# Connection.net
KiCad netlist of a schematic drawn in Altium Designer
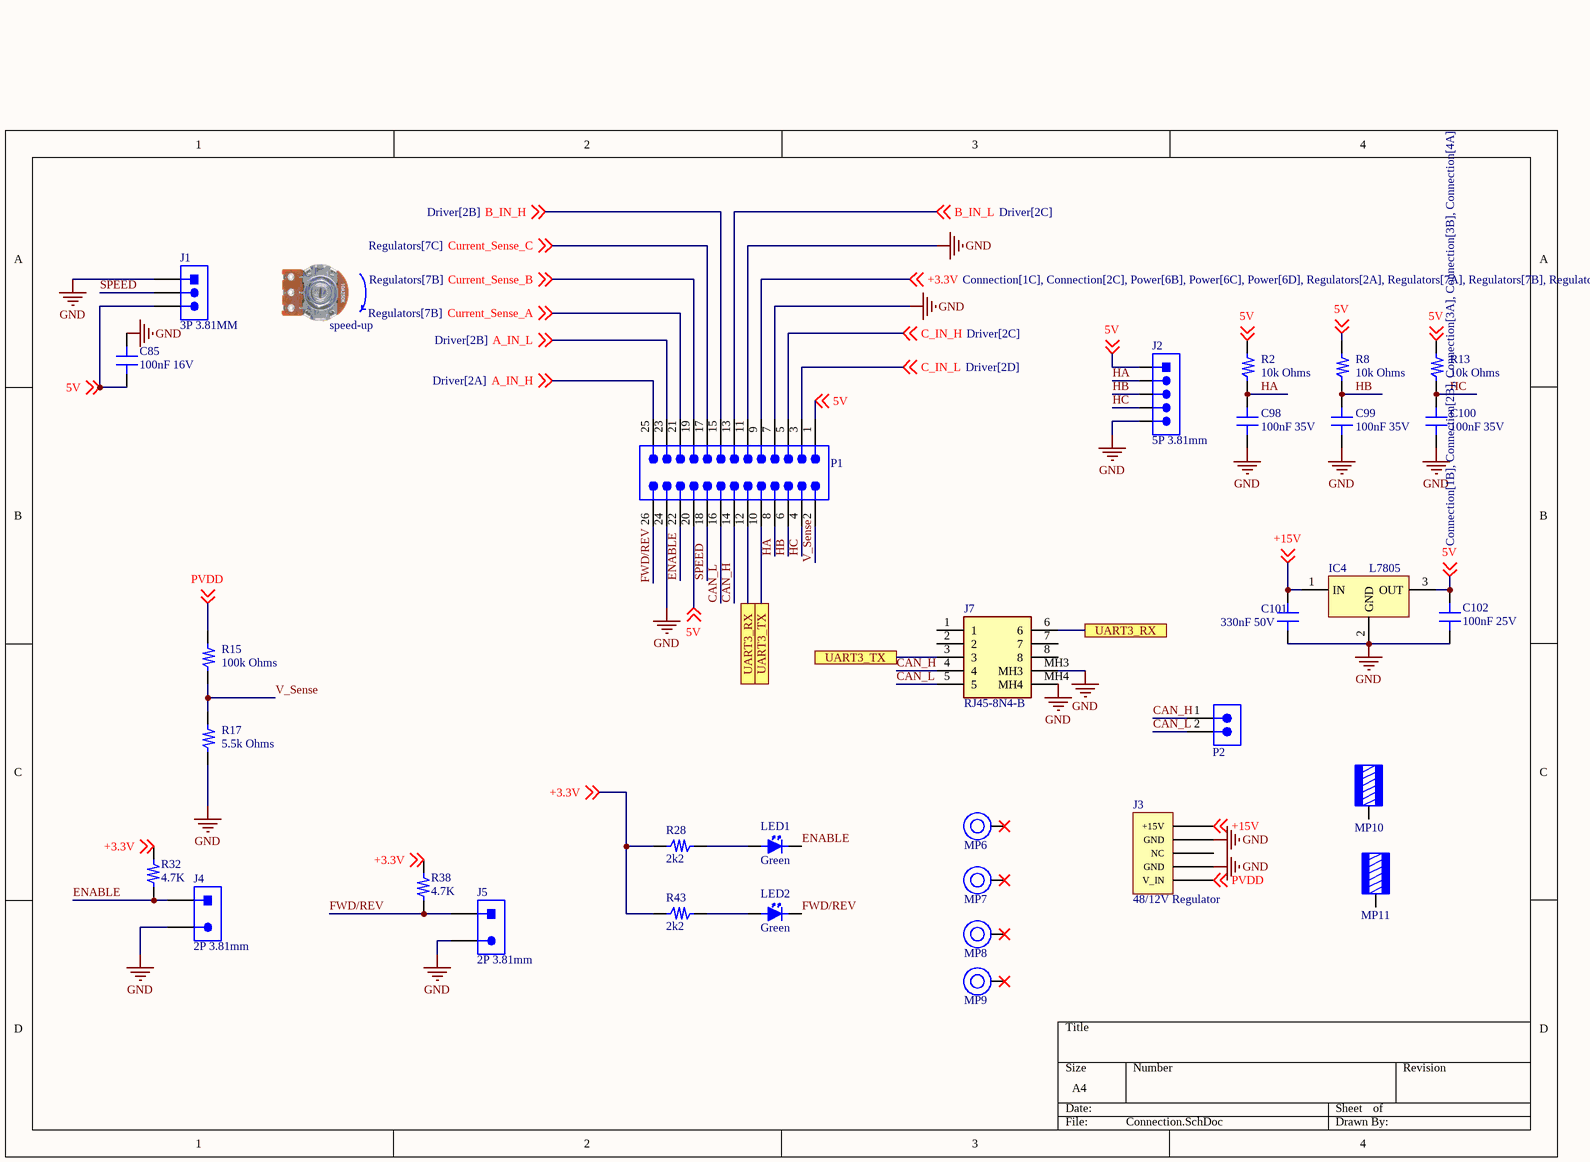
[diagram p0: Connection.SchDoc]

(export (version "E")
  (design (tool "Eeschema 10.0.6"))
  (components
    (comp (ref "C85")
      (value "100nF 16V")
      (footprint "0805_CAP")
      (libsource (lib "HidroanaSCHLib1") (part "CAP_0805"))
    )
    (comp (ref "C98")
      (value "100nF 35V")
      (footprint "0805_CAP")
      (libsource (lib "HidroanaSCHLib") (part "CAP_0805"))
    )
    (comp (ref "C99")
      (value "100nF 35V")
      (footprint "0805_CAP")
      (libsource (lib "HidroanaSCHLib") (part "CAP_0805"))
    )
    (comp (ref "C100")
      (value "100nF 35V")
      (footprint "0805_CAP")
      (libsource (lib "HidroanaSCHLib") (part "CAP_0805"))
    )
    (comp (ref "C101")
      (value "330nF 50V")
      (footprint "0805_CAP")
      (libsource (lib "HidroanaSCHLib") (part "CAP_0805"))
    )
    (comp (ref "C102")
      (value "100nF 25V")
      (footprint "0805_CAP")
      (libsource (lib "HidroanaSCHLib") (part "CAP_0805"))
    )
    (comp (ref "IC4")
      (value "L7805")
      (footprint "TO-220-3")
      (description "L7806CV-DG - IC-7806 V.REG.+5V 1.5A TO220 DOUBLE GAUGE ST")
      (libsource (lib "HidroanaSCHLib") (part "L7806"))
    )
    (comp (ref "J1")
      (value "3P 3.81MM")
      (footprint "TB3_3.81_90C")
      (description "15EDGRC-3.81-03P-11-00AH - TERM.BLK.3.81MM 3P 90C MALE GRAY CLOSED")
      (libsource (lib "HidroanaSCHLib") (part "TBLOCK3 3.81MM"))
    )
    (comp (ref "J2")
      (value "5P 3.81mm")
      (footprint "TB5 3.81MM")
      (description "15EDGRC-3.81-05P-14-00AH - TERM.BLK.3.81MM 5P 90C MALE GREEN CLOSED")
      (libsource (lib "HidroanaSCHLib") (part "TBLOCK5 3.81MM"))
    )
    (comp (ref "J3")
      (value "48/12V Regulator")
      (footprint "48/12V REGULATOR")
      (libsource (lib "HidroanaSCHLib") (part "48-12V REGULATOR"))
    )
    (comp (ref "J4")
      (value "2P 3.81mm")
      (footprint "TB2_3.81MM")
      (description "15EDGRC-3.81-02P-11-00AH - TERM.BLK.3.81MM 2P 90C MALE GRAY CLOSED")
      (libsource (lib "HidroanaSCHLib") (part "TBLOCK2 3.81MM"))
    )
    (comp (ref "J5")
      (value "2P 3.81mm")
      (footprint "TB2_3.81MM")
      (description "15EDGRC-3.81-02P-11-00AH - TERM.BLK.3.81MM 2P 90C MALE GRAY CLOSED")
      (libsource (lib "HidroanaSCHLib") (part "TBLOCK2 3.81MM"))
    )
    (comp (ref "J7")
      (value "RJ45-8N4-B")
      (footprint "RJ458N4B")
      (description "Modular Connectors / Ethernet Connectors 6 TRMN BRD/CBLE GRND 8 PIN BLOCK INDUCTOR")
      (fields (field (name "MOUSER PART NUMBER") "592-RJ45-8N4-B"))
      (libsource (lib "RJ45-8N4-B") (part "RJ45-8N4-B"))
    )
    (comp (ref "LED1")
      (value "Green")
      (footprint "0805LED")
      (description "0805")
      (libsource (lib "HidroanaSCHLib") (part "LED"))
    )
    (comp (ref "LED2")
      (value "Green")
      (footprint "0805LED")
      (description "0805")
      (libsource (lib "HidroanaSCHLib") (part "LED"))
    )
    (comp (ref "MP6")
      (value "M3 x 11mm")
      (footprint "9774110360")
      (description "WA-SMSI SMT Steel Spacer with internal Thread, OD 6mm, M3 x 11mm")
      (fields
        (field (name "MANUFACTURER PART NUMBER") "9774110360R")
        (field (name "MANUFACTURER") "Wurth Elektronik")
      )
      (libsource (lib "Altium_WA-SMSI (rev22a)") (part "9774110360R"))
    )
    (comp (ref "MP7")
      (value "M3 x 11mm")
      (footprint "9774110360")
      (description "WA-SMSI SMT Steel Spacer with internal Thread, OD 6mm, M3 x 11mm")
      (fields
        (field (name "MANUFACTURER PART NUMBER") "9774110360R")
        (field (name "MANUFACTURER") "Wurth Elektronik")
      )
      (libsource (lib "Altium_WA-SMSI (rev22a)") (part "9774110360R"))
    )
    (comp (ref "MP8")
      (value "M3 x 11mm")
      (footprint "9774110360")
      (description "WA-SMSI SMT Steel Spacer with internal Thread, OD 6mm, M3 x 11mm")
      (fields
        (field (name "MANUFACTURER PART NUMBER") "9774110360R")
        (field (name "MANUFACTURER") "Wurth Elektronik")
      )
      (libsource (lib "Altium_WA-SMSI (rev22a)") (part "9774110360R"))
    )
    (comp (ref "MP9")
      (value "M3 x 11mm")
      (footprint "9774110360")
      (description "WA-SMSI SMT Steel Spacer with internal Thread, OD 6mm, M3 x 11mm")
      (fields
        (field (name "MANUFACTURER PART NUMBER") "9774110360R")
        (field (name "MANUFACTURER") "Wurth Elektronik")
      )
      (libsource (lib "Altium_WA-SMSI (rev22a)") (part "9774110360R"))
    )
    (comp (ref "MP10")
      (value "M3")
      (footprint "7466303")
      (description "WP-SMRA REDCUBE SMT Right Angled without pins, M3, 50A")
      (fields
        (field (name "MANUFACTURER PART NUMBER") "7466303")
        (field (name "MANUFACTURER") "Wurth Elektronik")
      )
      (libsource (lib "Altium_WP-SMRA (rev22a) (1)") (part "7466303"))
    )
    (comp (ref "MP11")
      (value "M3")
      (footprint "7466303")
      (description "WP-SMRA REDCUBE SMT Right Angled without pins, M3, 50A")
      (fields
        (field (name "MANUFACTURER PART NUMBER") "7466303")
        (field (name "MANUFACTURER") "Wurth Elektronik")
      )
      (libsource (lib "Altium_WP-SMRA (rev22a) (1)") (part "7466303"))
    )
    (comp (ref "P1")
      (value "61302621121")
      (footprint "61302621121")
      (description "WR-PHD Pin Header, THT, Vertical, pitch 2.54mm, 2 Row, 26P")
      (fields (field (name "MANUFACTURER") "Wurth Elektronik"))
      (libsource (lib "Altium_WR-PHD (rev22b)") (part "61302621121"))
    )
    (comp (ref "P2")
      (value "61300211121")
      (footprint "61300211121")
      (description "WR-PHD Pin Header, THT, Vertical, pitch 2.54mm, 1 Row, 2P")
      (fields (field (name "MANUFACTURER") "Wurth Elektronik"))
      (libsource (lib "Altium_WR-PHD (rev24a)") (part "61300211121"))
    )
    (comp (ref "R2")
      (value "10k Ohms")
      (footprint "0805_RES")
      (description "0805")
      (fields (field (name "POWER") "1/8 W"))
      (libsource (lib "HidroanaSCHLib") (part "RES_0805"))
    )
    (comp (ref "R8")
      (value "10k Ohms")
      (footprint "0805_RES")
      (description "0805")
      (fields (field (name "POWER") "1/8 W"))
      (libsource (lib "HidroanaSCHLib") (part "RES_0805"))
    )
    (comp (ref "R13")
      (value "10k Ohms")
      (footprint "0805_RES")
      (description "0805")
      (fields (field (name "POWER") "1/8 W"))
      (libsource (lib "HidroanaSCHLib") (part "RES_0805"))
    )
    (comp (ref "R15")
      (value "100k Ohms")
      (footprint "0805_RES")
      (description "0805")
      (fields (field (name "POWER") "1/8 W"))
      (libsource (lib "HidroanaSCHLib") (part "RES_0805"))
    )
    (comp (ref "R17")
      (value "5.5k Ohms")
      (footprint "0805_RES")
      (description "0805")
      (fields (field (name "POWER") "1/8 W"))
      (libsource (lib "HidroanaSCHLib") (part "RES_0805"))
    )
    (comp (ref "R28")
      (value "2k2")
      (footprint "0603_RES")
      (description "0603")
      (fields (field (name "POWER") "1/8W"))
      (libsource (lib "HidroanaSCHLib") (part "RES_0603"))
    )
    (comp (ref "R32")
      (value "4.7K")
      (footprint "0603_RES")
      (description "0603")
      (fields (field (name "POWER") "1/8W"))
      (libsource (lib "HidroanaSCHLib") (part "RES_0603"))
    )
    (comp (ref "R38")
      (value "4.7K")
      (footprint "0603_RES")
      (description "0603")
      (fields (field (name "POWER") "1/8W"))
      (libsource (lib "HidroanaSCHLib") (part "RES_0603"))
    )
    (comp (ref "R43")
      (value "2k2")
      (footprint "0603_RES")
      (description "0603")
      (fields (field (name "POWER") "1/8W"))
      (libsource (lib "HidroanaSCHLib") (part "RES_0603"))
    )
  )
  (nets
    (net (code "1") (name "+3.3V") (class "Default")
      (node (ref "P1") (pin "9") (pinfunction "9_9") (pintype "passive"))
      (node (ref "R28") (pin "1") (pintype "passive"))
      (node (ref "R32") (pin "2") (pintype "passive"))
      (node (ref "R38") (pin "2") (pintype "passive"))
      (node (ref "R43") (pin "1") (pintype "passive"))
    )
    (net (code "2") (name "+15V") (class "Default")
      (node (ref "C101") (pin "2") (pinfunction "2_2") (pintype "passive"))
      (node (ref "IC4") (pin "1") (pinfunction "IN_1") (pintype "passive"))
      (node (ref "J3") (pin "1") (pinfunction "+15V_1") (pintype "passive"))
    )
    (net (code "3") (name "/CAN_H") (class "Default")
      (node (ref "J7") (pin "4") (pinfunction "4_4") (pintype "passive"))
      (node (ref "P1") (pin "14") (pinfunction "14_14") (pintype "passive"))
      (node (ref "P2") (pin "1") (pinfunction "1_1") (pintype "passive"))
    )
    (net (code "4") (name "/CAN_L") (class "Default")
      (node (ref "J7") (pin "5") (pinfunction "5_5") (pintype "passive"))
      (node (ref "P1") (pin "16") (pinfunction "16_16") (pintype "passive"))
      (node (ref "P2") (pin "2") (pinfunction "2_2") (pintype "passive"))
    )
    (net (code "5") (name "/ENABLE") (class "Default")
      (node (ref "J4") (pin "1") (pintype "passive"))
      (node (ref "LED1") (pin "2") (pinfunction "Cathode(-)_2") (pintype "passive"))
      (node (ref "P1") (pin "22") (pinfunction "22_22") (pintype "passive"))
      (node (ref "R32") (pin "1") (pintype "passive"))
    )
    (net (code "6") (name "/FWD{slash}REV") (class "Default")
      (node (ref "J5") (pin "1") (pintype "passive"))
      (node (ref "LED2") (pin "2") (pinfunction "Cathode(-)_2") (pintype "passive"))
      (node (ref "P1") (pin "26") (pinfunction "26_26") (pintype "passive"))
      (node (ref "R38") (pin "1") (pintype "passive"))
    )
    (net (code "7") (name "/HA") (class "Default")
      (node (ref "C98") (pin "2") (pinfunction "2_2") (pintype "passive"))
      (node (ref "J2") (pin "2") (pinfunction "2_2") (pintype "passive"))
      (node (ref "P1") (pin "8") (pinfunction "8_8") (pintype "passive"))
      (node (ref "R2") (pin "2") (pintype "passive"))
    )
    (net (code "8") (name "/HB") (class "Default")
      (node (ref "C99") (pin "2") (pinfunction "2_2") (pintype "passive"))
      (node (ref "J2") (pin "3") (pinfunction "3_3") (pintype "passive"))
      (node (ref "P1") (pin "6") (pinfunction "6_6") (pintype "passive"))
      (node (ref "R8") (pin "2") (pintype "passive"))
    )
    (net (code "9") (name "/HC") (class "Default")
      (node (ref "C100") (pin "2") (pinfunction "2_2") (pintype "passive"))
      (node (ref "J2") (pin "4") (pinfunction "4_4") (pintype "passive"))
      (node (ref "P1") (pin "4") (pinfunction "4_4") (pintype "passive"))
      (node (ref "R13") (pin "2") (pintype "passive"))
    )
    (net (code "10") (name "/SPEED") (class "Default")
      (node (ref "J1") (pin "2") (pinfunction "2_2") (pintype "passive"))
      (node (ref "P1") (pin "18") (pinfunction "18_18") (pintype "passive"))
    )
    (net (code "11") (name "/UART3_RX") (class "Default")
      (node (ref "J7") (pin "6") (pinfunction "6_6") (pintype "passive"))
      (node (ref "P1") (pin "12") (pinfunction "12_12") (pintype "passive"))
    )
    (net (code "12") (name "/UART3_TX") (class "Default")
      (node (ref "J7") (pin "3") (pinfunction "3_3") (pintype "passive"))
      (node (ref "P1") (pin "10") (pinfunction "10_10") (pintype "passive"))
    )
    (net (code "13") (name "/V_Sense") (class "Default")
      (node (ref "P1") (pin "2") (pinfunction "2_2") (pintype "passive"))
      (node (ref "R15") (pin "2") (pintype "passive"))
      (node (ref "R17") (pin "1") (pintype "passive"))
    )
    (net (code "14") (name "5V") (class "Default")
      (node (ref "C102") (pin "2") (pinfunction "2_2") (pintype "passive"))
      (node (ref "C85") (pin "2") (pinfunction "2_2") (pintype "passive"))
      (node (ref "IC4") (pin "3") (pinfunction "OUT_3") (pintype "passive"))
      (node (ref "J1") (pin "3") (pinfunction "3_3") (pintype "passive"))
      (node (ref "J2") (pin "1") (pinfunction "1_1") (pintype "passive"))
      (node (ref "P1") (pin "1") (pinfunction "1_1") (pintype "passive"))
      (node (ref "P1") (pin "20") (pinfunction "20_20") (pintype "passive"))
      (node (ref "R13") (pin "1") (pintype "passive"))
      (node (ref "R2") (pin "1") (pintype "passive"))
      (node (ref "R8") (pin "1") (pintype "passive"))
    )
    (net (code "15") (name "A_IN_H") (class "Default")
      (node (ref "P1") (pin "25") (pinfunction "25_25") (pintype "passive"))
    )
    (net (code "16") (name "A_IN_L") (class "Default")
      (node (ref "P1") (pin "23") (pinfunction "23_23") (pintype "passive"))
    )
    (net (code "17") (name "B_IN_H") (class "Default")
      (node (ref "P1") (pin "15") (pinfunction "15_15") (pintype "passive"))
    )
    (net (code "18") (name "B_IN_L") (class "Default")
      (node (ref "P1") (pin "13") (pinfunction "13_13") (pintype "passive"))
    )
    (net (code "19") (name "C_IN_H") (class "Default")
      (node (ref "P1") (pin "5") (pinfunction "5_5") (pintype "passive"))
    )
    (net (code "20") (name "C_IN_L") (class "Default")
      (node (ref "P1") (pin "3") (pinfunction "3_3") (pintype "passive"))
    )
    (net (code "21") (name "Current_Sense_A") (class "Default")
      (node (ref "P1") (pin "21") (pinfunction "21_21") (pintype "passive"))
    )
    (net (code "22") (name "Current_Sense_B") (class "Default")
      (node (ref "P1") (pin "19") (pinfunction "19_19") (pintype "passive"))
    )
    (net (code "23") (name "Current_Sense_C") (class "Default")
      (node (ref "P1") (pin "17") (pinfunction "17_17") (pintype "passive"))
    )
    (net (code "24") (name "GND") (class "Default")
      (node (ref "C100") (pin "1") (pinfunction "1_1") (pintype "passive"))
      (node (ref "C101") (pin "1") (pinfunction "1_1") (pintype "passive"))
      (node (ref "C102") (pin "1") (pinfunction "1_1") (pintype "passive"))
      (node (ref "C85") (pin "1") (pinfunction "1_1") (pintype "passive"))
      (node (ref "C98") (pin "1") (pinfunction "1_1") (pintype "passive"))
      (node (ref "C99") (pin "1") (pinfunction "1_1") (pintype "passive"))
      (node (ref "IC4") (pin "2") (pinfunction "GND_2") (pintype "passive"))
      (node (ref "J1") (pin "1") (pinfunction "1_1") (pintype "passive"))
      (node (ref "J2") (pin "5") (pinfunction "5_5") (pintype "passive"))
      (node (ref "J3") (pin "2") (pinfunction "GND_2") (pintype "passive"))
      (node (ref "J3") (pin "4") (pinfunction "GND_4") (pintype "passive"))
      (node (ref "J4") (pin "2") (pintype "passive"))
      (node (ref "J5") (pin "2") (pintype "passive"))
      (node (ref "J7") (pin "MH3") (pinfunction "MH3_MH3") (pintype "passive"))
      (node (ref "J7") (pin "MH4") (pinfunction "MH4_MH4") (pintype "passive"))
      (node (ref "P1") (pin "11") (pinfunction "11_11") (pintype "passive"))
      (node (ref "P1") (pin "24") (pinfunction "24_24") (pintype "passive"))
      (node (ref "P1") (pin "7") (pinfunction "7_7") (pintype "passive"))
      (node (ref "R17") (pin "2") (pintype "passive"))
    )
    (net (code "25") (name "Net-(LED1-Anode(+))") (class "Default")
      (node (ref "LED1") (pin "1") (pinfunction "Anode(+)_1") (pintype "passive"))
      (node (ref "R28") (pin "2") (pintype "passive"))
    )
    (net (code "26") (name "Net-(LED2-Anode(+))") (class "Default")
      (node (ref "LED2") (pin "1") (pinfunction "Anode(+)_1") (pintype "passive"))
      (node (ref "R43") (pin "2") (pintype "passive"))
    )
    (net (code "27") (name "PVDD") (class "Default")
      (node (ref "J3") (pin "5") (pinfunction "V_IN_5") (pintype "passive"))
      (node (ref "R15") (pin "1") (pintype "passive"))
    )
    (net (code "28") (name "unconnected-(J3-NC-Pad3)") (class "Default")
      (node (ref "J3") (pin "3") (pinfunction "NC_3") (pintype "passive"))
    )
    (net (code "29") (name "unconnected-(J7-Pad1)") (class "Default")
      (node (ref "J7") (pin "1") (pinfunction "1_1") (pintype "passive"))
    )
    (net (code "30") (name "unconnected-(J7-Pad2)") (class "Default")
      (node (ref "J7") (pin "2") (pinfunction "2_2") (pintype "passive"))
    )
    (net (code "31") (name "unconnected-(J7-Pad7)") (class "Default")
      (node (ref "J7") (pin "7") (pinfunction "7_7") (pintype "passive"))
    )
    (net (code "32") (name "unconnected-(J7-Pad8)") (class "Default")
      (node (ref "J7") (pin "8") (pinfunction "8_8") (pintype "passive"))
    )
    (net (code "33") (name "unconnected-(MP6-Pad1)") (class "Default")
      (node (ref "MP6") (pin "1") (pinfunction "1_1") (pintype "passive+no_connect"))
    )
    (net (code "34") (name "unconnected-(MP7-Pad1)") (class "Default")
      (node (ref "MP7") (pin "1") (pinfunction "1_1") (pintype "passive+no_connect"))
    )
    (net (code "35") (name "unconnected-(MP8-Pad1)") (class "Default")
      (node (ref "MP8") (pin "1") (pinfunction "1_1") (pintype "passive+no_connect"))
    )
    (net (code "36") (name "unconnected-(MP9-Pad1)") (class "Default")
      (node (ref "MP9") (pin "1") (pinfunction "1_1") (pintype "passive+no_connect"))
    )
    (net (code "37") (name "unconnected-(MP10-Pad1)") (class "Default")
      (node (ref "MP10") (pin "1") (pinfunction "1_1") (pintype "passive"))
    )
    (net (code "38") (name "unconnected-(MP11-Pad1)") (class "Default")
      (node (ref "MP11") (pin "1") (pinfunction "1_1") (pintype "passive"))
    )
  )
)
